# knob-ross-test1.net
KiCad netlist of a schematic drawn in EAGLE
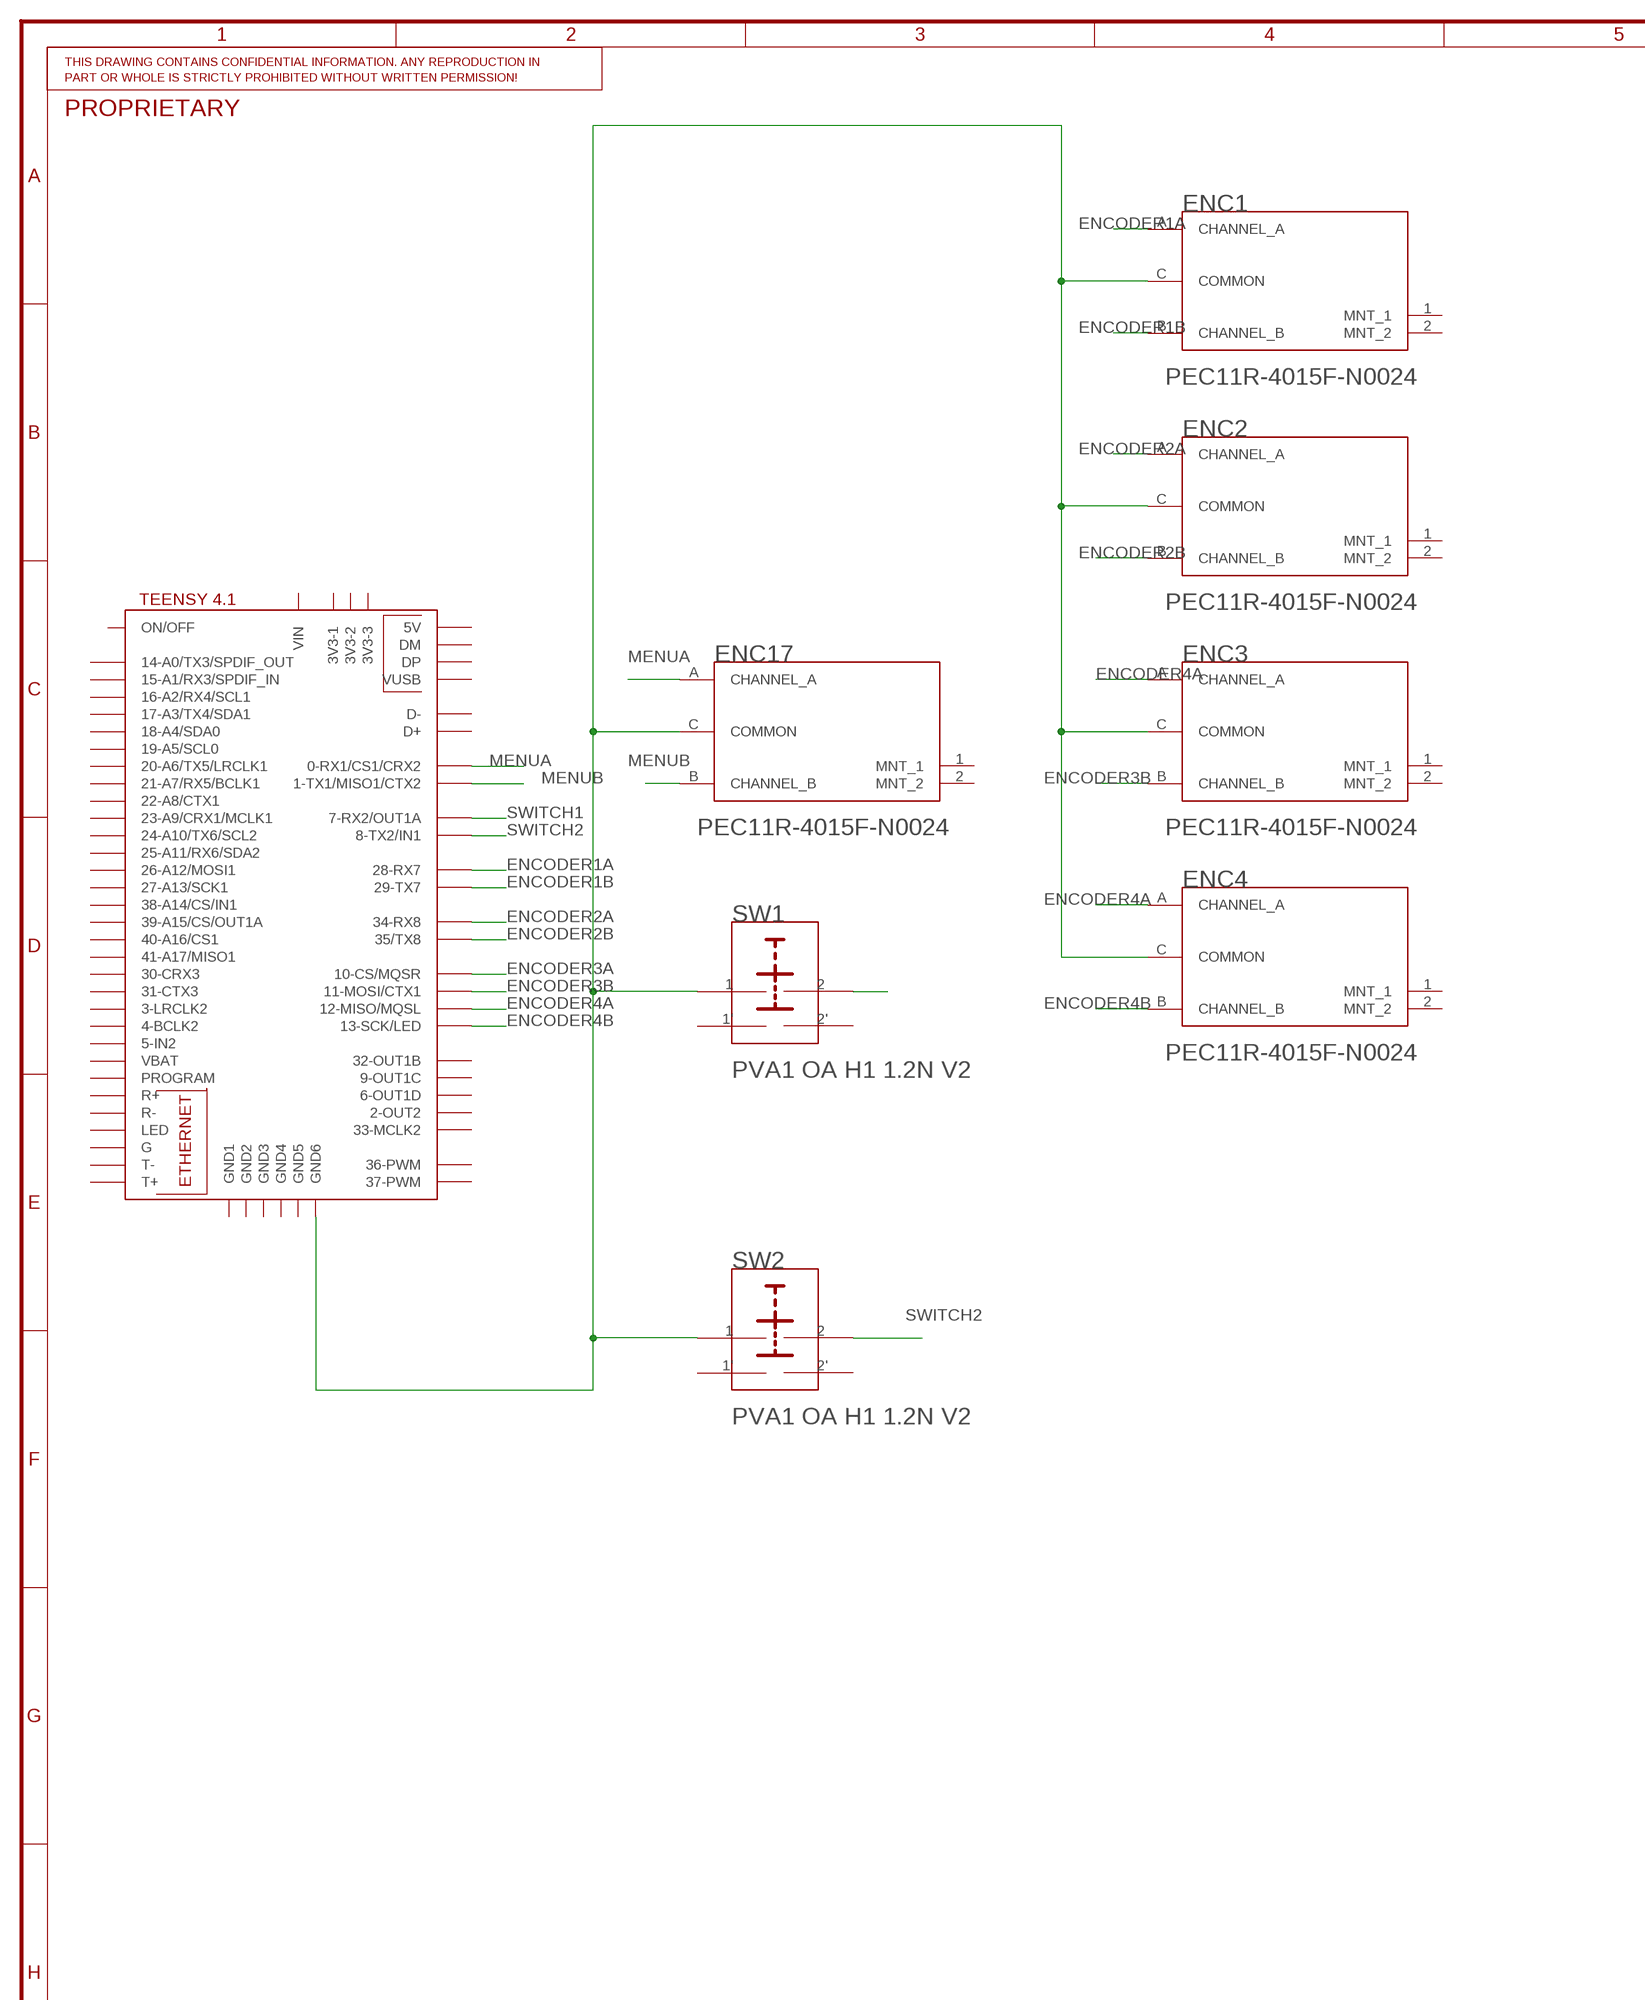
[diagram p0: schematic, sheet 1, part 1 of 2]
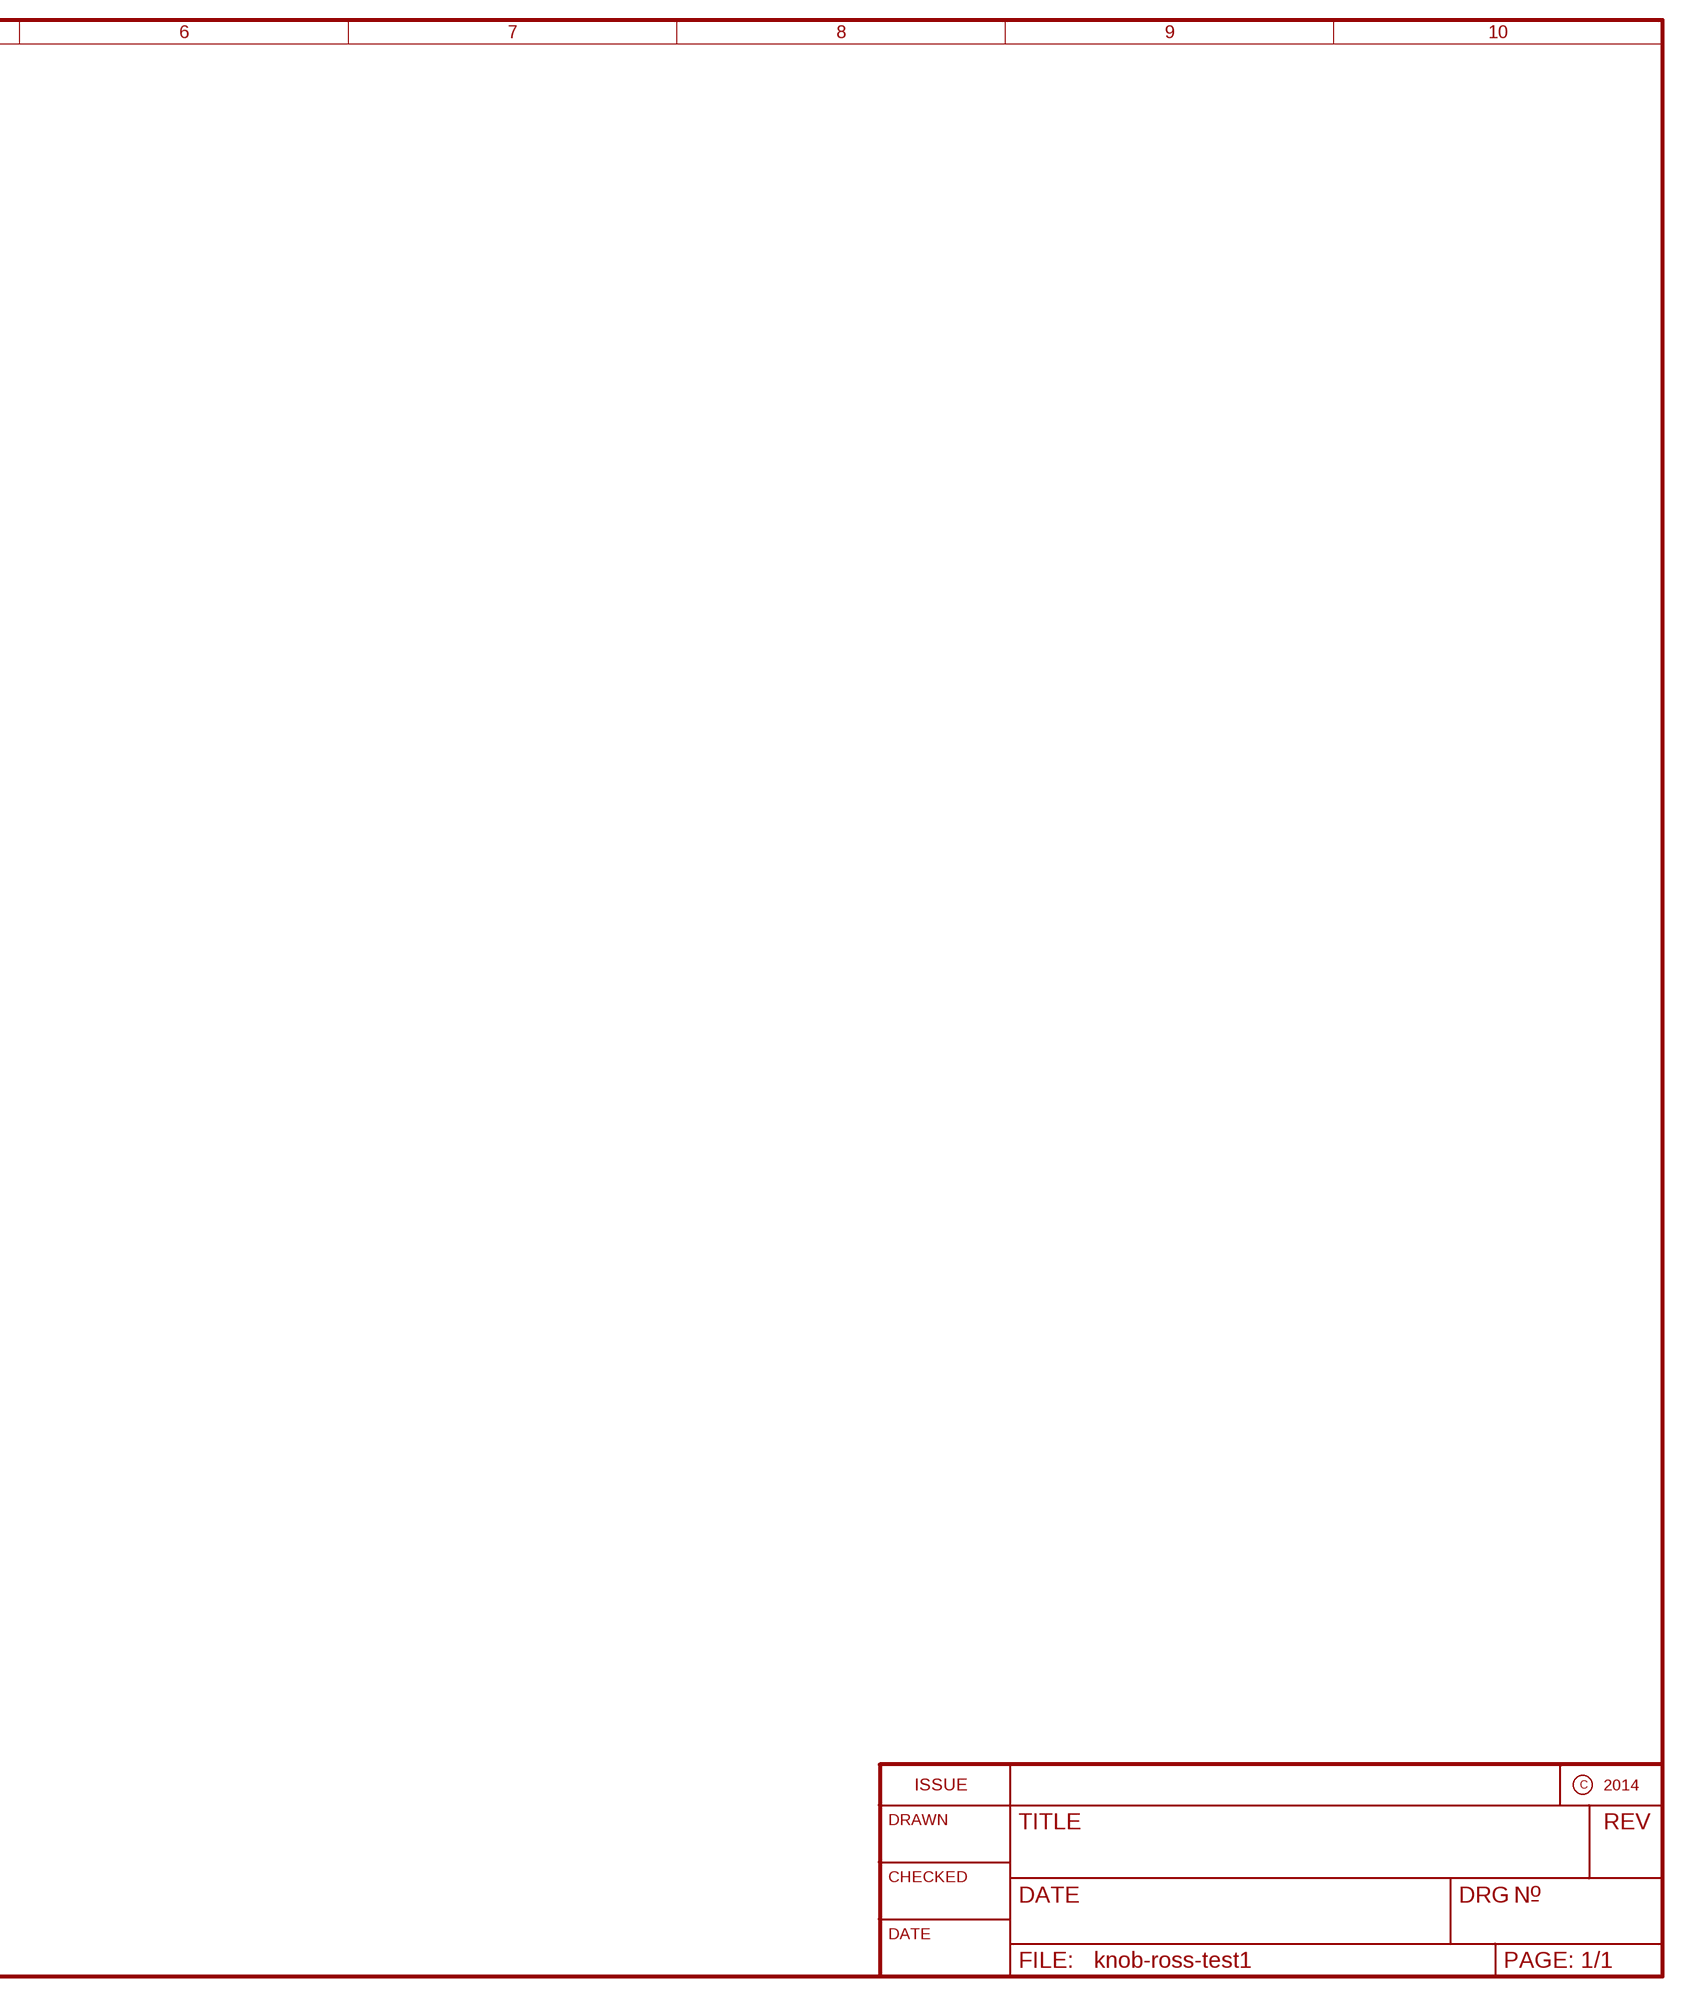
[diagram p1: schematic, sheet 1, part 2 of 2]

(export (version "E")
  (design (tool "Eeschema 10.0.6"))
  (components
    (comp (ref "ENC1")
      (value "BOURNS_PEC11R-4015F-N0024BOURNS_PEC11R-4015F-N0024_0_0")
      (footprint "eagle-import:BOURNS_PEC11R-4015F-N0024_0")
      (fields
        (field (name "DIGIKEY_PART_NUMBER") "PEC11R-4015F-N0024-ND")
        (field (name "MF") "Bourns")
        (field (name "MOUSER_PART_NUMBER") "652-PEC11R-4015F-N24")
      )
      (libsource (lib "eagle-import") (part "BOURNS_PEC11R-4015F-N0024BOURNS_PEC11R-4015F-N0024_0_0"))
    )
    (comp (ref "ENC2")
      (value "BOURNS_PEC11R-4015F-N0024BOURNS_PEC11R-4015F-N0024_0_0")
      (footprint "eagle-import:BOURNS_PEC11R-4015F-N0024_0")
      (fields
        (field (name "DIGIKEY_PART_NUMBER") "PEC11R-4015F-N0024-ND")
        (field (name "MF") "Bourns")
        (field (name "MOUSER_PART_NUMBER") "652-PEC11R-4015F-N24")
      )
      (libsource (lib "eagle-import") (part "BOURNS_PEC11R-4015F-N0024BOURNS_PEC11R-4015F-N0024_0_0"))
    )
    (comp (ref "ENC3")
      (value "BOURNS_PEC11R-4015F-N0024BOURNS_PEC11R-4015F-N0024_0_0")
      (footprint "eagle-import:BOURNS_PEC11R-4015F-N0024_0")
      (fields
        (field (name "DIGIKEY_PART_NUMBER") "PEC11R-4015F-N0024-ND")
        (field (name "MF") "Bourns")
        (field (name "MOUSER_PART_NUMBER") "652-PEC11R-4015F-N24")
      )
      (libsource (lib "eagle-import") (part "BOURNS_PEC11R-4015F-N0024BOURNS_PEC11R-4015F-N0024_0_0"))
    )
    (comp (ref "ENC4")
      (value "BOURNS_PEC11R-4015F-N0024BOURNS_PEC11R-4015F-N0024_0_0")
      (footprint "eagle-import:BOURNS_PEC11R-4015F-N0024_0")
      (fields
        (field (name "DIGIKEY_PART_NUMBER") "PEC11R-4015F-N0024-ND")
        (field (name "MF") "Bourns")
        (field (name "MOUSER_PART_NUMBER") "652-PEC11R-4015F-N24")
      )
      (libsource (lib "eagle-import") (part "BOURNS_PEC11R-4015F-N0024BOURNS_PEC11R-4015F-N0024_0_0"))
    )
    (comp (ref "ENC17")
      (value "BOURNS_PEC11R-4015F-N0024BOURNS_PEC11R-4015F-N0024_0_0")
      (footprint "eagle-import:BOURNS_PEC11R-4015F-N0024_0")
      (fields
        (field (name "DIGIKEY_PART_NUMBER") "PEC11R-4015F-N0024-ND")
        (field (name "MF") "Bourns")
        (field (name "MOUSER_PART_NUMBER") "652-PEC11R-4015F-N24")
      )
      (libsource (lib "eagle-import") (part "BOURNS_PEC11R-4015F-N0024BOURNS_PEC11R-4015F-N0024_0_0"))
    )
    (comp (ref "SW1")
      (value "C&K_COMPONENTS_PVA1_OA_H1_1_2N_V2C&K_COMPONENTS_PVA1_OA_H1_1_2N_V2_0_0")
      (footprint "eagle-import:C&K_COMPONENTS_PVA1_OA_H1_1_2N_V2_0")
      (fields
        (field (name "DIGIKEY_PART_NUMBER") "401-1133-ND")
        (field (name "MF") "C&K Components")
        (field (name "MOUSER_PART_NUMBER") "611-PVA1OAH11.2NV2")
      )
      (libsource (lib "eagle-import") (part "C&K_COMPONENTS_PVA1_OA_H1_1_2N_V2C&K_COMPONENTS_PVA1_OA_H1_1_2N_V2_0_0"))
    )
    (comp (ref "SW2")
      (value "C&K_COMPONENTS_PVA1_OA_H1_1_2N_V2C&K_COMPONENTS_PVA1_OA_H1_1_2N_V2_0_0")
      (footprint "eagle-import:C&K_COMPONENTS_PVA1_OA_H1_1_2N_V2_0")
      (fields
        (field (name "DIGIKEY_PART_NUMBER") "401-1133-ND")
        (field (name "MF") "C&K Components")
        (field (name "MOUSER_PART_NUMBER") "611-PVA1OAH11.2NV2")
      )
      (libsource (lib "eagle-import") (part "C&K_COMPONENTS_PVA1_OA_H1_1_2N_V2C&K_COMPONENTS_PVA1_OA_H1_1_2N_V2_0_0"))
    )
    (comp (ref "U$1")
      (value "TEENSY41")
      (footprint "eagle-import:TEENSY41")
      (libsource (lib "eagle-import") (part "TEENSY41"))
    )
  )
  (nets
    (net (code "1") (name "/ENCODER1A") (class "Default")
      (node (ref "ENC1") (pin "A") (pinfunction "CHANNEL_A_A") (pintype "passive"))
      (node (ref "U$1") (pin "28-RX7") (pinfunction "28-RX7_28-RX7") (pintype "bidirectional"))
    )
    (net (code "2") (name "/ENCODER1B") (class "Default")
      (node (ref "ENC1") (pin "B") (pinfunction "CHANNEL_B_B") (pintype "passive"))
      (node (ref "U$1") (pin "29-TX7") (pinfunction "29-TX7_29-TX7") (pintype "bidirectional"))
    )
    (net (code "3") (name "/ENCODER2A") (class "Default")
      (node (ref "ENC2") (pin "A") (pinfunction "CHANNEL_A_A") (pintype "passive"))
      (node (ref "U$1") (pin "34-RX8") (pinfunction "34-RX8_34-RX8") (pintype "bidirectional"))
    )
    (net (code "4") (name "/ENCODER2B") (class "Default")
      (node (ref "ENC2") (pin "B") (pinfunction "CHANNEL_B_B") (pintype "passive"))
      (node (ref "U$1") (pin "35-TX8") (pinfunction "35/TX8_35-TX8") (pintype "bidirectional"))
    )
    (net (code "5") (name "/ENCODER3A") (class "Default")
      (node (ref "U$1") (pin "10-CS\\MQSR") (pinfunction "10-CS/MQSR_10-CS\\MQSR") (pintype "bidirectional"))
    )
    (net (code "6") (name "/ENCODER3B") (class "Default")
      (node (ref "ENC3") (pin "B") (pinfunction "CHANNEL_B_B") (pintype "passive"))
      (node (ref "U$1") (pin "11-MOSI/CTX1") (pinfunction "11-MOSI/CTX1_11-MOSI/CTX1") (pintype "bidirectional"))
    )
    (net (code "7") (name "/ENCODER4A") (class "Default")
      (node (ref "ENC3") (pin "A") (pinfunction "CHANNEL_A_A") (pintype "passive"))
      (node (ref "ENC4") (pin "A") (pinfunction "CHANNEL_A_A") (pintype "passive"))
      (node (ref "U$1") (pin "12-MISO/MQSL") (pinfunction "12-MISO/MQSL_12-MISO/MQSL") (pintype "bidirectional"))
    )
    (net (code "8") (name "/ENCODER4B") (class "Default")
      (node (ref "ENC4") (pin "B") (pinfunction "CHANNEL_B_B") (pintype "passive"))
      (node (ref "U$1") (pin "13-SCK/LED") (pinfunction "13-SCK/LED_13-SCK/LED") (pintype "bidirectional"))
    )
    (net (code "9") (name "/MENUA") (class "Default")
      (node (ref "ENC17") (pin "A") (pinfunction "CHANNEL_A_A") (pintype "passive"))
      (node (ref "U$1") (pin "0-RX1/CS1/CRX2") (pinfunction "0-RX1/CS1/CRX2_0-RX1/CS1/CRX2") (pintype "bidirectional"))
    )
    (net (code "10") (name "/MENUB") (class "Default")
      (node (ref "ENC17") (pin "B") (pinfunction "CHANNEL_B_B") (pintype "passive"))
      (node (ref "U$1") (pin "1-TX1/MISO1/CTX2") (pinfunction "1-TX1/MISO1/CTX2_1-TX1/MISO1/CTX2") (pintype "bidirectional"))
    )
    (net (code "11") (name "/SWITCH1") (class "Default")
      (node (ref "SW1") (pin "2") (pinfunction "2_2") (pintype "passive"))
      (node (ref "U$1") (pin "7-RX2/OUT1A") (pinfunction "7-RX2/OUT1A_7-RX2/OUT1A") (pintype "bidirectional"))
    )
    (net (code "12") (name "/SWITCH2") (class "Default")
      (node (ref "SW2") (pin "2") (pinfunction "2_2") (pintype "passive"))
      (node (ref "U$1") (pin "8-TX2/IN1") (pinfunction "8-TX2/IN1_8-TX2/IN1") (pintype "bidirectional"))
    )
    (net (code "13") (name "Net-(ENC1-COMMON)") (class "Default")
      (node (ref "ENC1") (pin "C") (pinfunction "COMMON_C") (pintype "passive"))
      (node (ref "ENC17") (pin "C") (pinfunction "COMMON_C") (pintype "passive"))
      (node (ref "ENC2") (pin "C") (pinfunction "COMMON_C") (pintype "passive"))
      (node (ref "ENC3") (pin "C") (pinfunction "COMMON_C") (pintype "passive"))
      (node (ref "ENC4") (pin "C") (pinfunction "COMMON_C") (pintype "passive"))
      (node (ref "SW1") (pin "1") (pinfunction "1_1") (pintype "passive"))
      (node (ref "SW2") (pin "1") (pinfunction "1_1") (pintype "passive"))
      (node (ref "U$1") (pin "GND6") (pinfunction "GND6_GND6") (pintype "bidirectional"))
    )
    (net (code "14") (name "unconnected-(ENC1-MNT_1-Pad1)") (class "Default")
      (node (ref "ENC1") (pin "1") (pinfunction "MNT_1_1") (pintype "passive"))
    )
    (net (code "15") (name "unconnected-(ENC1-MNT_2-Pad2)") (class "Default")
      (node (ref "ENC1") (pin "2") (pinfunction "MNT_2_2") (pintype "passive"))
    )
    (net (code "16") (name "unconnected-(ENC2-MNT_1-Pad1)") (class "Default")
      (node (ref "ENC2") (pin "1") (pinfunction "MNT_1_1") (pintype "passive"))
    )
    (net (code "17") (name "unconnected-(ENC2-MNT_2-Pad2)") (class "Default")
      (node (ref "ENC2") (pin "2") (pinfunction "MNT_2_2") (pintype "passive"))
    )
    (net (code "18") (name "unconnected-(ENC3-MNT_1-Pad1)") (class "Default")
      (node (ref "ENC3") (pin "1") (pinfunction "MNT_1_1") (pintype "passive"))
    )
    (net (code "19") (name "unconnected-(ENC3-MNT_2-Pad2)") (class "Default")
      (node (ref "ENC3") (pin "2") (pinfunction "MNT_2_2") (pintype "passive"))
    )
    (net (code "20") (name "unconnected-(ENC4-MNT_1-Pad1)") (class "Default")
      (node (ref "ENC4") (pin "1") (pinfunction "MNT_1_1") (pintype "passive"))
    )
    (net (code "21") (name "unconnected-(ENC4-MNT_2-Pad2)") (class "Default")
      (node (ref "ENC4") (pin "2") (pinfunction "MNT_2_2") (pintype "passive"))
    )
    (net (code "22") (name "unconnected-(ENC17-MNT_1-Pad1)") (class "Default")
      (node (ref "ENC17") (pin "1") (pinfunction "MNT_1_1") (pintype "passive"))
    )
    (net (code "23") (name "unconnected-(ENC17-MNT_2-Pad2)") (class "Default")
      (node (ref "ENC17") (pin "2") (pinfunction "MNT_2_2") (pintype "passive"))
    )
    (net (code "24") (name "unconnected-(SW1-Pad1')") (class "Default")
      (node (ref "SW1") (pin "1'") (pinfunction "1'_1'") (pintype "passive"))
    )
    (net (code "25") (name "unconnected-(SW1-Pad2')") (class "Default")
      (node (ref "SW1") (pin "2'") (pinfunction "2'_2'") (pintype "passive"))
    )
    (net (code "26") (name "unconnected-(SW2-Pad1')") (class "Default")
      (node (ref "SW2") (pin "1'") (pinfunction "1'_1'") (pintype "passive"))
    )
    (net (code "27") (name "unconnected-(SW2-Pad2')") (class "Default")
      (node (ref "SW2") (pin "2'") (pinfunction "2'_2'") (pintype "passive"))
    )
    (net (code "28") (name "unconnected-(U$1-5V-Pad+5V)") (class "Default")
      (node (ref "U$1") (pin "+5V") (pinfunction "5V_+5V") (pintype "bidirectional"))
    )
    (net (code "29") (name "unconnected-(U$1-Pad2-OUT2)") (class "Default")
      (node (ref "U$1") (pin "2-OUT2") (pinfunction "2-OUT2_2-OUT2") (pintype "bidirectional"))
    )
    (net (code "30") (name "unconnected-(U$1-Pad3-LRCLK2)") (class "Default")
      (node (ref "U$1") (pin "3-LRCLK2") (pinfunction "3-LRCLK2_3-LRCLK2") (pintype "bidirectional"))
    )
    (net (code "31") (name "unconnected-(U$1-Pad3V3-1)") (class "Default")
      (node (ref "U$1") (pin "3V3-1") (pinfunction "3V3-1_3V3-1") (pintype "bidirectional"))
    )
    (net (code "32") (name "unconnected-(U$1-Pad3V3-2)") (class "Default")
      (node (ref "U$1") (pin "3V3-2") (pinfunction "3V3-2_3V3-2") (pintype "bidirectional"))
    )
    (net (code "33") (name "unconnected-(U$1-Pad3V3-3)") (class "Default")
      (node (ref "U$1") (pin "3V3-3") (pinfunction "3V3-3_3V3-3") (pintype "bidirectional"))
    )
    (net (code "34") (name "unconnected-(U$1-Pad4-BCLK2)") (class "Default")
      (node (ref "U$1") (pin "4-BCLK2") (pinfunction "4-BCLK2_4-BCLK2") (pintype "bidirectional"))
    )
    (net (code "35") (name "unconnected-(U$1-Pad5-IN2)") (class "Default")
      (node (ref "U$1") (pin "5-IN2") (pinfunction "5-IN2_5-IN2") (pintype "bidirectional"))
    )
    (net (code "36") (name "unconnected-(U$1-Pad6-OUT1D)") (class "Default")
      (node (ref "U$1") (pin "6-OUT1D") (pinfunction "6-OUT1D_6-OUT1D") (pintype "bidirectional"))
    )
    (net (code "37") (name "unconnected-(U$1-Pad9-OUT1C)") (class "Default")
      (node (ref "U$1") (pin "9-OUT1C") (pinfunction "9-OUT1C_9-OUT1C") (pintype "bidirectional"))
    )
    (net (code "38") (name "unconnected-(U$1-Pad14-A0{slash}TX3{slash}SPDIF_OUT)") (class "Default")
      (node (ref "U$1") (pin "14-A0/TX3/SPDIF_OUT") (pinfunction "14-A0/TX3/SPDIF_OUT_14-A0/TX3/SPDIF_OUT") (pintype "bidirectional"))
    )
    (net (code "39") (name "unconnected-(U$1-Pad15-A1{slash}RX3{slash}SPDIF_IN)") (class "Default")
      (node (ref "U$1") (pin "15-A1/RX3/SPDIF_IN") (pinfunction "15-A1/RX3/SPDIF_IN_15-A1/RX3/SPDIF_IN") (pintype "bidirectional"))
    )
    (net (code "40") (name "unconnected-(U$1-Pad16-A2{slash}RX4{slash}SCL1)") (class "Default")
      (node (ref "U$1") (pin "16-A2/RX4/SCL1") (pinfunction "16-A2/RX4/SCL1_16-A2/RX4/SCL1") (pintype "bidirectional"))
    )
    (net (code "41") (name "unconnected-(U$1-Pad17-A3{slash}TX4{slash}SDA1)") (class "Default")
      (node (ref "U$1") (pin "17-A3/TX4/SDA1") (pinfunction "17-A3/TX4/SDA1_17-A3/TX4/SDA1") (pintype "bidirectional"))
    )
    (net (code "42") (name "unconnected-(U$1-Pad18-A4{slash}SDA0)") (class "Default")
      (node (ref "U$1") (pin "18-A4/SDA0") (pinfunction "18-A4/SDA0_18-A4/SDA0") (pintype "bidirectional"))
    )
    (net (code "43") (name "unconnected-(U$1-Pad19-A5{slash}SCL0)") (class "Default")
      (node (ref "U$1") (pin "19-A5/SCL0") (pinfunction "19-A5/SCL0_19-A5/SCL0") (pintype "bidirectional"))
    )
    (net (code "44") (name "unconnected-(U$1-Pad20-A6{slash}TX5{slash}LRCLK1)") (class "Default")
      (node (ref "U$1") (pin "20-A6/TX5/LRCLK1") (pinfunction "20-A6/TX5/LRCLK1_20-A6/TX5/LRCLK1") (pintype "bidirectional"))
    )
    (net (code "45") (name "unconnected-(U$1-Pad21-A7{slash}RX5{slash}BCLK1)") (class "Default")
      (node (ref "U$1") (pin "21-A7/RX5/BCLK1") (pinfunction "21-A7/RX5/BCLK1_21-A7/RX5/BCLK1") (pintype "bidirectional"))
    )
    (net (code "46") (name "unconnected-(U$1-Pad22-A8{slash}CTX1)") (class "Default")
      (node (ref "U$1") (pin "22-A8/CTX1") (pinfunction "22-A8/CTX1_22-A8/CTX1") (pintype "bidirectional"))
    )
    (net (code "47") (name "unconnected-(U$1-Pad23-A9{slash}CRX1{slash}MCLK1)") (class "Default")
      (node (ref "U$1") (pin "23-A9/CRX1/MCLK1") (pinfunction "23-A9/CRX1/MCLK1_23-A9/CRX1/MCLK1") (pintype "bidirectional"))
    )
    (net (code "48") (name "unconnected-(U$1-Pad24-A10{slash}TX6{slash}SCL2)") (class "Default")
      (node (ref "U$1") (pin "24-A10/TX6/SCL2") (pinfunction "24-A10/TX6/SCL2_24-A10/TX6/SCL2") (pintype "bidirectional"))
    )
    (net (code "49") (name "unconnected-(U$1-Pad25-A11{slash}RX6{slash}SDA2)") (class "Default")
      (node (ref "U$1") (pin "25-A11/RX6/SDA2") (pinfunction "25-A11/RX6/SDA2_25-A11/RX6/SDA2") (pintype "bidirectional"))
    )
    (net (code "50") (name "unconnected-(U$1-Pad26-A12{slash}MOSI1)") (class "Default")
      (node (ref "U$1") (pin "26-A12/MOSI1") (pinfunction "26-A12/MOSI1_26-A12/MOSI1") (pintype "bidirectional"))
    )
    (net (code "51") (name "unconnected-(U$1-Pad27-A13{slash}SCK1)") (class "Default")
      (node (ref "U$1") (pin "27-A13/SCK1") (pinfunction "27-A13/SCK1_27-A13/SCK1") (pintype "bidirectional"))
    )
    (net (code "52") (name "unconnected-(U$1-Pad30-CRX3)") (class "Default")
      (node (ref "U$1") (pin "30-CRX3") (pinfunction "30-CRX3_30-CRX3") (pintype "bidirectional"))
    )
    (net (code "53") (name "unconnected-(U$1-Pad31-CTX3)") (class "Default")
      (node (ref "U$1") (pin "31-CTX3") (pinfunction "31-CTX3_31-CTX3") (pintype "bidirectional"))
    )
    (net (code "54") (name "unconnected-(U$1-Pad32-OUT1B)") (class "Default")
      (node (ref "U$1") (pin "32-OUT1B") (pinfunction "32-OUT1B_32-OUT1B") (pintype "bidirectional"))
    )
    (net (code "55") (name "unconnected-(U$1-Pad33-MCLK2)") (class "Default")
      (node (ref "U$1") (pin "33-MCLK2") (pinfunction "33-MCLK2_33-MCLK2") (pintype "bidirectional"))
    )
    (net (code "56") (name "unconnected-(U$1-Pad36-PWM)") (class "Default")
      (node (ref "U$1") (pin "36-PWM") (pinfunction "36-PWM_36-PWM") (pintype "bidirectional"))
    )
    (net (code "57") (name "unconnected-(U$1-Pad37-PWM)") (class "Default")
      (node (ref "U$1") (pin "37-PWM") (pinfunction "37-PWM_37-PWM") (pintype "bidirectional"))
    )
    (net (code "58") (name "unconnected-(U$1-Pad38-A14{slash}CS{slash}IN1)") (class "Default")
      (node (ref "U$1") (pin "38-A14/CS/IN1") (pinfunction "38-A14/CS/IN1_38-A14/CS/IN1") (pintype "bidirectional"))
    )
    (net (code "59") (name "unconnected-(U$1-Pad39-A15{slash}CS{slash}OUT1A)") (class "Default")
      (node (ref "U$1") (pin "39-A15/CS/OUT1A") (pinfunction "39-A15/CS/OUT1A_39-A15/CS/OUT1A") (pintype "bidirectional"))
    )
    (net (code "60") (name "unconnected-(U$1-Pad40-A16{slash}CS1)") (class "Default")
      (node (ref "U$1") (pin "40-A16/CS1") (pinfunction "40-A16/CS1_40-A16/CS1") (pintype "bidirectional"))
    )
    (net (code "61") (name "unconnected-(U$1-Pad41-A17{slash}MISO1)") (class "Default")
      (node (ref "U$1") (pin "41-A17/MISO1") (pinfunction "41-A17/MISO1_41-A17/MISO1") (pintype "bidirectional"))
    )
    (net (code "62") (name "unconnected-(U$1-PadD+)") (class "Default")
      (node (ref "U$1") (pin "D+") (pinfunction "D+_D+") (pintype "bidirectional"))
    )
    (net (code "63") (name "unconnected-(U$1-PadD-)") (class "Default")
      (node (ref "U$1") (pin "D-") (pinfunction "D-_D-") (pintype "bidirectional"))
    )
    (net (code "64") (name "unconnected-(U$1-PadDM)") (class "Default")
      (node (ref "U$1") (pin "DM") (pinfunction "DM_DM") (pintype "bidirectional"))
    )
    (net (code "65") (name "unconnected-(U$1-PadDP)") (class "Default")
      (node (ref "U$1") (pin "DP") (pinfunction "DP_DP") (pintype "bidirectional"))
    )
    (net (code "66") (name "unconnected-(U$1-PadG)") (class "Default")
      (node (ref "U$1") (pin "G") (pinfunction "G_G") (pintype "bidirectional"))
    )
    (net (code "67") (name "unconnected-(U$1-PadGND1)") (class "Default")
      (node (ref "U$1") (pin "GND1") (pinfunction "GND1_GND1") (pintype "bidirectional"))
    )
    (net (code "68") (name "unconnected-(U$1-PadGND2)") (class "Default")
      (node (ref "U$1") (pin "GND2") (pinfunction "GND2_GND2") (pintype "bidirectional"))
    )
    (net (code "69") (name "unconnected-(U$1-PadGND3)") (class "Default")
      (node (ref "U$1") (pin "GND3") (pinfunction "GND3_GND3") (pintype "bidirectional"))
    )
    (net (code "70") (name "unconnected-(U$1-PadGND4)") (class "Default")
      (node (ref "U$1") (pin "GND4") (pinfunction "GND4_GND4") (pintype "bidirectional"))
    )
    (net (code "71") (name "unconnected-(U$1-PadGND5)") (class "Default")
      (node (ref "U$1") (pin "GND5") (pinfunction "GND5_GND5") (pintype "bidirectional"))
    )
    (net (code "72") (name "unconnected-(U$1-PadLED)") (class "Default")
      (node (ref "U$1") (pin "LED") (pinfunction "LED_LED") (pintype "bidirectional"))
    )
    (net (code "73") (name "unconnected-(U$1-PadON{slash}OFF)") (class "Default")
      (node (ref "U$1") (pin "ON/OFF") (pinfunction "ON/OFF_ON/OFF") (pintype "bidirectional"))
    )
    (net (code "74") (name "unconnected-(U$1-PadPROGRAM)") (class "Default")
      (node (ref "U$1") (pin "PROGRAM") (pinfunction "PROGRAM_PROGRAM") (pintype "bidirectional"))
    )
    (net (code "75") (name "unconnected-(U$1-PadR+)") (class "Default")
      (node (ref "U$1") (pin "R+") (pinfunction "R+_R+") (pintype "bidirectional"))
    )
    (net (code "76") (name "unconnected-(U$1-PadR-)") (class "Default")
      (node (ref "U$1") (pin "R-") (pinfunction "R-_R-") (pintype "bidirectional"))
    )
    (net (code "77") (name "unconnected-(U$1-PadT+)") (class "Default")
      (node (ref "U$1") (pin "T+") (pinfunction "T+_T+") (pintype "bidirectional"))
    )
    (net (code "78") (name "unconnected-(U$1-PadT-)") (class "Default")
      (node (ref "U$1") (pin "T-") (pinfunction "T-_T-") (pintype "bidirectional"))
    )
    (net (code "79") (name "unconnected-(U$1-PadVBAT)") (class "Default")
      (node (ref "U$1") (pin "VBAT") (pinfunction "VBAT_VBAT") (pintype "bidirectional"))
    )
    (net (code "80") (name "unconnected-(U$1-PadVIN)") (class "Default")
      (node (ref "U$1") (pin "VIN") (pinfunction "VIN_VIN") (pintype "bidirectional"))
    )
    (net (code "81") (name "unconnected-(U$1-PadVUSB)") (class "Default")
      (node (ref "U$1") (pin "VUSB") (pinfunction "VUSB_VUSB") (pintype "bidirectional"))
    )
  )
)
